# Sunboost.net
KiCad netlist of a schematic drawn in Altium Designer
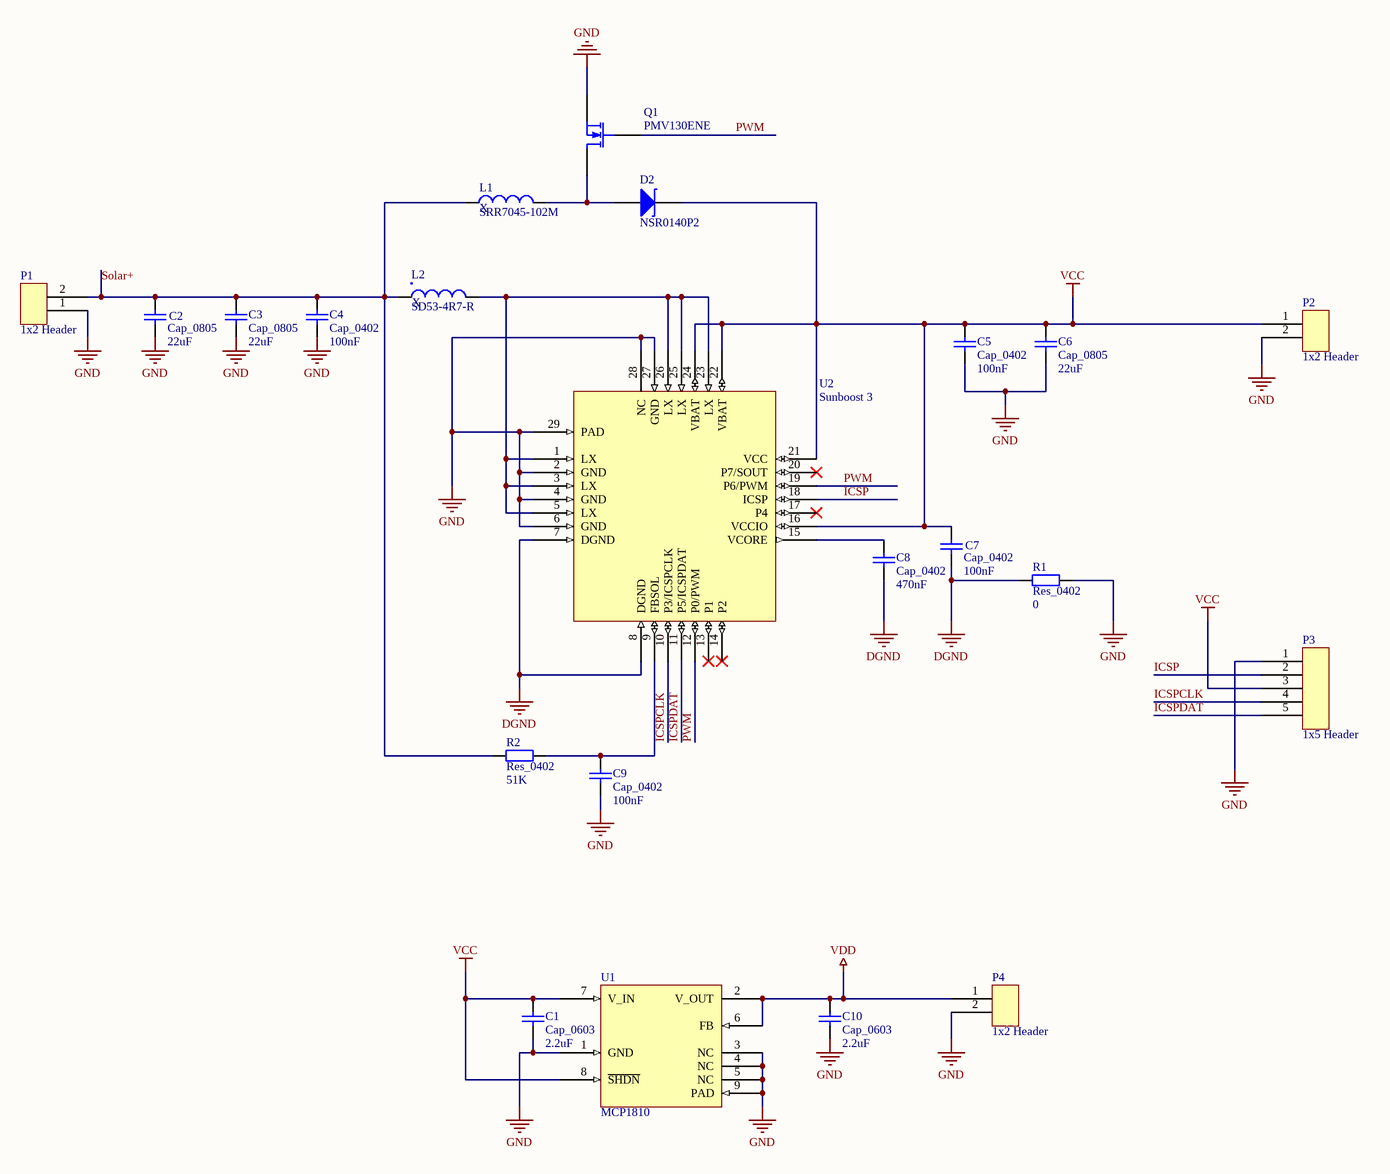
[diagram p0: Sunboost.SchDoc]

(export (version "E")
  (design (tool "Eeschema 10.0.6"))
  (components
    (comp (ref "C1")
      (value "Cap_0603")
      (footprint "0603")
      (description "Capacitor")
      (fields (field (name "ALTIUM_VALUE") "2.2uF") (field (name "PUBLISHER") "Altium Limited"))
      (libsource (lib "Schematic_Components") (part "Cap_0603"))
    )
    (comp (ref "C2")
      (value "Cap_0805")
      (footprint "0805")
      (description "Capacitor")
      (fields (field (name "ALTIUM_VALUE") "22uF") (field (name "PUBLISHER") "Altium Limited"))
      (libsource (lib "Schematic_Components") (part "Cap_0805"))
    )
    (comp (ref "C3")
      (value "Cap_0805")
      (footprint "0805")
      (description "Capacitor")
      (fields (field (name "ALTIUM_VALUE") "22uF") (field (name "PUBLISHER") "Altium Limited"))
      (libsource (lib "Schematic_Components") (part "Cap_0805"))
    )
    (comp (ref "C4")
      (value "Cap_0402")
      (footprint "0402")
      (description "Capacitor")
      (fields (field (name "ALTIUM_VALUE") "100nF") (field (name "PUBLISHER") "Altium Limited"))
      (libsource (lib "Schematic_Components") (part "Cap_0402"))
    )
    (comp (ref "C5")
      (value "Cap_0402")
      (footprint "0402")
      (description "Capacitor")
      (fields (field (name "ALTIUM_VALUE") "100nF") (field (name "PUBLISHER") "Altium Limited"))
      (libsource (lib "Schematic_Components") (part "Cap_0402"))
    )
    (comp (ref "C6")
      (value "Cap_0805")
      (footprint "0805")
      (description "Capacitor")
      (fields (field (name "ALTIUM_VALUE") "22uF") (field (name "PUBLISHER") "Altium Limited"))
      (libsource (lib "Schematic_Components") (part "Cap_0805"))
    )
    (comp (ref "C7")
      (value "Cap_0402")
      (footprint "0402")
      (description "Capacitor")
      (fields (field (name "ALTIUM_VALUE") "100nF") (field (name "PUBLISHER") "Altium Limited"))
      (libsource (lib "Schematic_Components") (part "Cap_0402"))
    )
    (comp (ref "C8")
      (value "Cap_0402")
      (footprint "0402")
      (description "Capacitor")
      (fields (field (name "ALTIUM_VALUE") "470nF") (field (name "PUBLISHER") "Altium Limited"))
      (libsource (lib "Schematic_Components") (part "Cap_0402"))
    )
    (comp (ref "C9")
      (value "Cap_0402")
      (footprint "0402")
      (description "Capacitor")
      (fields (field (name "ALTIUM_VALUE") "100nF") (field (name "PUBLISHER") "Altium Limited"))
      (libsource (lib "Schematic_Components") (part "Cap_0402"))
    )
    (comp (ref "C10")
      (value "Cap_0603")
      (footprint "0603")
      (description "Capacitor")
      (fields (field (name "ALTIUM_VALUE") "2.2uF") (field (name "PUBLISHER") "Altium Limited"))
      (libsource (lib "Schematic_Components") (part "Cap_0603"))
    )
    (comp (ref "D2")
      (value "NSR0140P2")
      (footprint "SOD-923")
      (description "Typical INFRARED GaAs LED")
      (fields (field (name "PUBLISHER") "Altium Limited"))
      (libsource (lib "Schematic_Components") (part "NSR0140P2"))
    )
    (comp (ref "L1")
      (value "SRR7045-102M")
      (footprint "SRR7045-102M")
      (description "Inductor")
      (fields (field (name "ALTIUM_VALUE") "X"))
      (libsource (lib "Schematic_Components") (part "SRR7045-102M"))
    )
    (comp (ref "L2")
      (value "SD53-4R7-R")
      (footprint "SD53-4R7-R")
      (description "Inductor")
      (fields (field (name "ALTIUM_VALUE") "X"))
      (libsource (lib "Schematic_Components") (part "SD53-4R7-R"))
    )
    (comp (ref "P1")
      (value "1x2 Header")
      (footprint "1x2 Header 1.27")
      (libsource (lib "") (part "1x2 Header_1"))
    )
    (comp (ref "P2")
      (value "1x2 Header")
      (footprint "1x2 Header 1.27")
      (libsource (lib "Schematic_Components") (part "1x2 Header"))
    )
    (comp (ref "P3")
      (value "1x5 Header")
      (footprint "1x5 Header 1.27")
      (libsource (lib "Schematic_Components") (part "1x5 Header"))
    )
    (comp (ref "P4")
      (value "1x2 Header")
      (footprint "1x2 Header 1.27")
      (libsource (lib "Schematic_Components") (part "1x2 Header"))
    )
    (comp (ref "Q1")
      (value "PMV130ENE")
      (footprint "SOT-23")
      (description "N-Channel MOSFET")
      (fields (field (name "PUBLISHER") "Altium Limited"))
      (libsource (lib "Schematic_Components") (part "PMV130ENE"))
    )
    (comp (ref "R1")
      (value "Res_0402")
      (footprint "0402")
      (description "Resistor")
      (fields (field (name "ALTIUM_VALUE") "0") (field (name "PUBLISHER") "Altium Limited"))
      (libsource (lib "Schematic_Components") (part "Res_0402"))
    )
    (comp (ref "R2")
      (value "Res_0402")
      (footprint "0402")
      (description "Resistor")
      (fields (field (name "ALTIUM_VALUE") "51K") (field (name "PUBLISHER") "Altium Limited"))
      (libsource (lib "Schematic_Components") (part "Res_0402"))
    )
    (comp (ref "U1")
      (value "MCP1810")
      (footprint "VDFN8")
      (description "3V Regulator, 150 mA")
      (libsource (lib "Schematic_Components") (part "MCP1810"))
    )
    (comp (ref "U2")
      (value "Sunboost 3")
      (footprint "28-QFN_0.4mm")
      (description "Initvation Sunboost 3")
      (libsource (lib "Schematic_Components") (part "Sunboost 3"))
    )
  )
  (nets
    (net (code "1") (name "/ICSP") (class "Default")
      (node (ref "P3") (pin "2") (pintype "passive"))
      (node (ref "U2") (pin "18") (pinfunction "ICSP_18") (pintype "bidirectional"))
    )
    (net (code "2") (name "/ICSPCLK") (class "Default")
      (node (ref "P3") (pin "4") (pintype "passive"))
      (node (ref "U2") (pin "10") (pinfunction "P3/ICSPCLK_10") (pintype "bidirectional"))
    )
    (net (code "3") (name "/ICSPDAT") (class "Default")
      (node (ref "P3") (pin "5") (pintype "passive"))
      (node (ref "U2") (pin "11") (pinfunction "P5/ICSPDAT_11") (pintype "bidirectional"))
    )
    (net (code "4") (name "/PWM") (class "Default")
      (node (ref "Q1") (pin "1") (pinfunction "G_1") (pintype "passive"))
      (node (ref "U2") (pin "12") (pinfunction "P0/PWM_12") (pintype "bidirectional"))
      (node (ref "U2") (pin "19") (pinfunction "P6/PWM_19") (pintype "bidirectional"))
    )
    (net (code "5") (name "/Solar+") (class "Default")
      (node (ref "C2") (pin "2") (pinfunction "2_2") (pintype "passive"))
      (node (ref "C3") (pin "2") (pinfunction "2_2") (pintype "passive"))
      (node (ref "C4") (pin "2") (pinfunction "2_2") (pintype "passive"))
      (node (ref "L1") (pin "1") (pinfunction "1_1") (pintype "passive"))
      (node (ref "L2") (pin "1") (pinfunction "1_1") (pintype "passive"))
      (node (ref "P1") (pin "2") (pintype "passive"))
      (node (ref "R2") (pin "1") (pinfunction "1_1") (pintype "passive"))
    )
    (net (code "6") (name "DGND") (class "Default")
      (node (ref "C7") (pin "1") (pinfunction "1_1") (pintype "passive"))
      (node (ref "C8") (pin "1") (pinfunction "1_1") (pintype "passive"))
      (node (ref "R1") (pin "1") (pinfunction "1_1") (pintype "passive"))
      (node (ref "U2") (pin "7") (pinfunction "DGND_7") (pintype "input"))
      (node (ref "U2") (pin "8") (pinfunction "DGND_8") (pintype "input"))
    )
    (net (code "7") (name "GND") (class "Default")
      (node (ref "C1") (pin "1") (pinfunction "1_1") (pintype "passive"))
      (node (ref "C10") (pin "1") (pinfunction "1_1") (pintype "passive"))
      (node (ref "C2") (pin "1") (pinfunction "1_1") (pintype "passive"))
      (node (ref "C3") (pin "1") (pinfunction "1_1") (pintype "passive"))
      (node (ref "C4") (pin "1") (pinfunction "1_1") (pintype "passive"))
      (node (ref "C5") (pin "1") (pinfunction "1_1") (pintype "passive"))
      (node (ref "C6") (pin "1") (pinfunction "1_1") (pintype "passive"))
      (node (ref "C9") (pin "1") (pinfunction "1_1") (pintype "passive"))
      (node (ref "P1") (pin "1") (pintype "passive"))
      (node (ref "P2") (pin "2") (pintype "passive"))
      (node (ref "P3") (pin "1") (pintype "passive"))
      (node (ref "P4") (pin "2") (pintype "passive"))
      (node (ref "Q1") (pin "2") (pinfunction "S_2") (pintype "passive"))
      (node (ref "R1") (pin "2") (pinfunction "2_2") (pintype "passive"))
      (node (ref "U1") (pin "1") (pinfunction "GND_1") (pintype "input"))
      (node (ref "U1") (pin "3") (pinfunction "NC_3") (pintype "passive"))
      (node (ref "U1") (pin "4") (pinfunction "NC_4") (pintype "passive"))
      (node (ref "U1") (pin "5") (pinfunction "NC_5") (pintype "passive"))
      (node (ref "U1") (pin "9") (pinfunction "PAD_9") (pintype "input"))
      (node (ref "U2") (pin "2") (pinfunction "GND_2") (pintype "input"))
      (node (ref "U2") (pin "27") (pinfunction "GND_27") (pintype "input"))
      (node (ref "U2") (pin "28") (pinfunction "NC_28") (pintype "passive"))
      (node (ref "U2") (pin "29") (pinfunction "PAD_29") (pintype "input"))
      (node (ref "U2") (pin "4") (pinfunction "GND_4") (pintype "input"))
      (node (ref "U2") (pin "6") (pinfunction "GND_6") (pintype "input"))
    )
    (net (code "8") (name "Net-(D2-A)") (class "Default")
      (node (ref "D2") (pin "2") (pinfunction "A_2") (pintype "passive"))
      (node (ref "L1") (pin "2") (pinfunction "2_2") (pintype "passive"))
      (node (ref "Q1") (pin "3") (pinfunction "D_3") (pintype "passive"))
    )
    (net (code "9") (name "Net-(L2-Pad2)") (class "Default")
      (node (ref "L2") (pin "2") (pinfunction "2_2") (pintype "passive"))
      (node (ref "U2") (pin "1") (pinfunction "LX_1") (pintype "input"))
      (node (ref "U2") (pin "23") (pinfunction "LX_23") (pintype "input"))
      (node (ref "U2") (pin "25") (pinfunction "LX_25") (pintype "input"))
      (node (ref "U2") (pin "26") (pinfunction "LX_26") (pintype "input"))
      (node (ref "U2") (pin "3") (pinfunction "LX_3") (pintype "input"))
      (node (ref "U2") (pin "5") (pinfunction "LX_5") (pintype "input"))
    )
    (net (code "10") (name "Net-(U2-FBSOL)") (class "Default")
      (node (ref "C9") (pin "2") (pinfunction "2_2") (pintype "passive"))
      (node (ref "R2") (pin "2") (pinfunction "2_2") (pintype "passive"))
      (node (ref "U2") (pin "9") (pinfunction "FBSOL_9") (pintype "bidirectional"))
    )
    (net (code "11") (name "Net-(U2-VCORE)") (class "Default")
      (node (ref "C8") (pin "2") (pinfunction "2_2") (pintype "passive"))
      (node (ref "U2") (pin "15") (pinfunction "VCORE_15") (pintype "output"))
    )
    (net (code "12") (name "VCC") (class "Default")
      (node (ref "C1") (pin "2") (pinfunction "2_2") (pintype "passive"))
      (node (ref "C5") (pin "2") (pinfunction "2_2") (pintype "passive"))
      (node (ref "C6") (pin "2") (pinfunction "2_2") (pintype "passive"))
      (node (ref "C7") (pin "2") (pinfunction "2_2") (pintype "passive"))
      (node (ref "D2") (pin "1") (pinfunction "K_1") (pintype "passive"))
      (node (ref "P2") (pin "1") (pintype "passive"))
      (node (ref "P3") (pin "3") (pintype "passive"))
      (node (ref "U1") (pin "7") (pinfunction "V_IN_7") (pintype "input"))
      (node (ref "U1") (pin "8") (pinfunction "~{SHDN}_8") (pintype "input"))
      (node (ref "U2") (pin "16") (pinfunction "VCCIO_16") (pintype "bidirectional"))
      (node (ref "U2") (pin "21") (pinfunction "VCC_21") (pintype "bidirectional"))
      (node (ref "U2") (pin "22") (pinfunction "VBAT_22") (pintype "bidirectional"))
      (node (ref "U2") (pin "24") (pinfunction "VBAT_24") (pintype "bidirectional"))
    )
    (net (code "13") (name "VDD") (class "Default")
      (node (ref "C10") (pin "2") (pinfunction "2_2") (pintype "passive"))
      (node (ref "P4") (pin "1") (pintype "passive"))
      (node (ref "U1") (pin "2") (pinfunction "V_OUT_2") (pintype "passive"))
      (node (ref "U1") (pin "6") (pinfunction "FB_6") (pintype "input"))
    )
    (net (code "14") (name "unconnected-(U2-P1-Pad13)") (class "Default")
      (node (ref "U2") (pin "13") (pinfunction "P1_13") (pintype "bidirectional+no_connect"))
    )
    (net (code "15") (name "unconnected-(U2-P2-Pad14)") (class "Default")
      (node (ref "U2") (pin "14") (pinfunction "P2_14") (pintype "bidirectional+no_connect"))
    )
    (net (code "16") (name "unconnected-(U2-P4-Pad17)") (class "Default")
      (node (ref "U2") (pin "17") (pinfunction "P4_17") (pintype "bidirectional+no_connect"))
    )
    (net (code "17") (name "unconnected-(U2-P7{slash}SOUT-Pad20)") (class "Default")
      (node (ref "U2") (pin "20") (pinfunction "P7/SOUT_20") (pintype "bidirectional+no_connect"))
    )
  )
)
